# SubBus13.net
KiCad netlist of a schematic drawn in Altium Designer
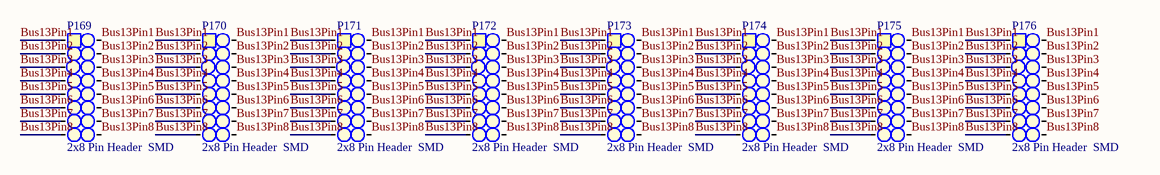
[diagram p0: SubBus13.SchDoc]

(export (version "E")
  (design (tool "Eeschema 10.0.6"))
  (components
    (comp (ref "P169")
      (value "2x8 Pin Header  SMD")
      (footprint "2X8_SMD_PH_2.54")
      (description "2.54mm, SMD")
      (libsource (lib "jclib") (part "2x8 Pin Header  SMD"))
    )
    (comp (ref "P170")
      (value "2x8 Pin Header  SMD")
      (footprint "2X8_SMD_PH_2.54")
      (description "2.54mm, SMD")
      (libsource (lib "jclib") (part "2x8 Pin Header  SMD"))
    )
    (comp (ref "P171")
      (value "2x8 Pin Header  SMD")
      (footprint "2X8_SMD_PH_2.54")
      (description "2.54mm, SMD")
      (libsource (lib "jclib") (part "2x8 Pin Header  SMD"))
    )
    (comp (ref "P172")
      (value "2x8 Pin Header  SMD")
      (footprint "2X8_SMD_PH_2.54")
      (description "2.54mm, SMD")
      (libsource (lib "jclib") (part "2x8 Pin Header  SMD"))
    )
    (comp (ref "P173")
      (value "2x8 Pin Header  SMD")
      (footprint "2X8_SMD_PH_2.54")
      (description "2.54mm, SMD")
      (libsource (lib "jclib") (part "2x8 Pin Header  SMD"))
    )
    (comp (ref "P174")
      (value "2x8 Pin Header  SMD")
      (footprint "2X8_SMD_PH_2.54")
      (description "2.54mm, SMD")
      (libsource (lib "jclib") (part "2x8 Pin Header  SMD"))
    )
    (comp (ref "P175")
      (value "2x8 Pin Header  SMD")
      (footprint "2X8_SMD_PH_2.54")
      (description "2.54mm, SMD")
      (libsource (lib "jclib") (part "2x8 Pin Header  SMD"))
    )
    (comp (ref "P176")
      (value "2x8 Pin Header  SMD")
      (footprint "2X8_SMD_PH_2.54")
      (description "2.54mm, SMD")
      (libsource (lib "jclib") (part "2x8 Pin Header  SMD"))
    )
  )
  (nets
    (net (code "1") (name "/Bus13Pin1") (class "Default")
      (node (ref "P169") (pin "1") (pinfunction "1_1") (pintype "passive"))
      (node (ref "P169") (pin "16") (pinfunction "16_16") (pintype "passive"))
      (node (ref "P170") (pin "1") (pinfunction "1_1") (pintype "passive"))
      (node (ref "P170") (pin "16") (pinfunction "16_16") (pintype "passive"))
      (node (ref "P171") (pin "1") (pinfunction "1_1") (pintype "passive"))
      (node (ref "P171") (pin "16") (pinfunction "16_16") (pintype "passive"))
      (node (ref "P172") (pin "1") (pinfunction "1_1") (pintype "passive"))
      (node (ref "P172") (pin "16") (pinfunction "16_16") (pintype "passive"))
      (node (ref "P173") (pin "1") (pinfunction "1_1") (pintype "passive"))
      (node (ref "P173") (pin "16") (pinfunction "16_16") (pintype "passive"))
      (node (ref "P174") (pin "1") (pinfunction "1_1") (pintype "passive"))
      (node (ref "P174") (pin "16") (pinfunction "16_16") (pintype "passive"))
      (node (ref "P175") (pin "1") (pinfunction "1_1") (pintype "passive"))
      (node (ref "P175") (pin "16") (pinfunction "16_16") (pintype "passive"))
      (node (ref "P176") (pin "1") (pinfunction "1_1") (pintype "passive"))
      (node (ref "P176") (pin "16") (pinfunction "16_16") (pintype "passive"))
    )
    (net (code "2") (name "/Bus13Pin2") (class "Default")
      (node (ref "P169") (pin "15") (pinfunction "15_15") (pintype "passive"))
      (node (ref "P169") (pin "2") (pinfunction "2_2") (pintype "passive"))
      (node (ref "P170") (pin "15") (pinfunction "15_15") (pintype "passive"))
      (node (ref "P170") (pin "2") (pinfunction "2_2") (pintype "passive"))
      (node (ref "P171") (pin "15") (pinfunction "15_15") (pintype "passive"))
      (node (ref "P171") (pin "2") (pinfunction "2_2") (pintype "passive"))
      (node (ref "P172") (pin "15") (pinfunction "15_15") (pintype "passive"))
      (node (ref "P172") (pin "2") (pinfunction "2_2") (pintype "passive"))
      (node (ref "P173") (pin "15") (pinfunction "15_15") (pintype "passive"))
      (node (ref "P173") (pin "2") (pinfunction "2_2") (pintype "passive"))
      (node (ref "P174") (pin "15") (pinfunction "15_15") (pintype "passive"))
      (node (ref "P174") (pin "2") (pinfunction "2_2") (pintype "passive"))
      (node (ref "P175") (pin "15") (pinfunction "15_15") (pintype "passive"))
      (node (ref "P175") (pin "2") (pinfunction "2_2") (pintype "passive"))
      (node (ref "P176") (pin "15") (pinfunction "15_15") (pintype "passive"))
      (node (ref "P176") (pin "2") (pinfunction "2_2") (pintype "passive"))
    )
    (net (code "3") (name "/Bus13Pin3") (class "Default")
      (node (ref "P169") (pin "14") (pinfunction "14_14") (pintype "passive"))
      (node (ref "P169") (pin "3") (pinfunction "3_3") (pintype "passive"))
      (node (ref "P170") (pin "14") (pinfunction "14_14") (pintype "passive"))
      (node (ref "P170") (pin "3") (pinfunction "3_3") (pintype "passive"))
      (node (ref "P171") (pin "14") (pinfunction "14_14") (pintype "passive"))
      (node (ref "P171") (pin "3") (pinfunction "3_3") (pintype "passive"))
      (node (ref "P172") (pin "14") (pinfunction "14_14") (pintype "passive"))
      (node (ref "P172") (pin "3") (pinfunction "3_3") (pintype "passive"))
      (node (ref "P173") (pin "14") (pinfunction "14_14") (pintype "passive"))
      (node (ref "P173") (pin "3") (pinfunction "3_3") (pintype "passive"))
      (node (ref "P174") (pin "14") (pinfunction "14_14") (pintype "passive"))
      (node (ref "P174") (pin "3") (pinfunction "3_3") (pintype "passive"))
      (node (ref "P175") (pin "14") (pinfunction "14_14") (pintype "passive"))
      (node (ref "P175") (pin "3") (pinfunction "3_3") (pintype "passive"))
      (node (ref "P176") (pin "14") (pinfunction "14_14") (pintype "passive"))
      (node (ref "P176") (pin "3") (pinfunction "3_3") (pintype "passive"))
    )
    (net (code "4") (name "/Bus13Pin4") (class "Default")
      (node (ref "P169") (pin "13") (pinfunction "13_13") (pintype "passive"))
      (node (ref "P169") (pin "4") (pinfunction "4_4") (pintype "passive"))
      (node (ref "P170") (pin "13") (pinfunction "13_13") (pintype "passive"))
      (node (ref "P170") (pin "4") (pinfunction "4_4") (pintype "passive"))
      (node (ref "P171") (pin "13") (pinfunction "13_13") (pintype "passive"))
      (node (ref "P171") (pin "4") (pinfunction "4_4") (pintype "passive"))
      (node (ref "P172") (pin "13") (pinfunction "13_13") (pintype "passive"))
      (node (ref "P172") (pin "4") (pinfunction "4_4") (pintype "passive"))
      (node (ref "P173") (pin "13") (pinfunction "13_13") (pintype "passive"))
      (node (ref "P173") (pin "4") (pinfunction "4_4") (pintype "passive"))
      (node (ref "P174") (pin "13") (pinfunction "13_13") (pintype "passive"))
      (node (ref "P174") (pin "4") (pinfunction "4_4") (pintype "passive"))
      (node (ref "P175") (pin "13") (pinfunction "13_13") (pintype "passive"))
      (node (ref "P175") (pin "4") (pinfunction "4_4") (pintype "passive"))
      (node (ref "P176") (pin "13") (pinfunction "13_13") (pintype "passive"))
      (node (ref "P176") (pin "4") (pinfunction "4_4") (pintype "passive"))
    )
    (net (code "5") (name "/Bus13Pin5") (class "Default")
      (node (ref "P169") (pin "12") (pinfunction "12_12") (pintype "passive"))
      (node (ref "P169") (pin "5") (pinfunction "5_5") (pintype "passive"))
      (node (ref "P170") (pin "12") (pinfunction "12_12") (pintype "passive"))
      (node (ref "P170") (pin "5") (pinfunction "5_5") (pintype "passive"))
      (node (ref "P171") (pin "12") (pinfunction "12_12") (pintype "passive"))
      (node (ref "P171") (pin "5") (pinfunction "5_5") (pintype "passive"))
      (node (ref "P172") (pin "12") (pinfunction "12_12") (pintype "passive"))
      (node (ref "P172") (pin "5") (pinfunction "5_5") (pintype "passive"))
      (node (ref "P173") (pin "12") (pinfunction "12_12") (pintype "passive"))
      (node (ref "P173") (pin "5") (pinfunction "5_5") (pintype "passive"))
      (node (ref "P174") (pin "12") (pinfunction "12_12") (pintype "passive"))
      (node (ref "P174") (pin "5") (pinfunction "5_5") (pintype "passive"))
      (node (ref "P175") (pin "12") (pinfunction "12_12") (pintype "passive"))
      (node (ref "P175") (pin "5") (pinfunction "5_5") (pintype "passive"))
      (node (ref "P176") (pin "12") (pinfunction "12_12") (pintype "passive"))
      (node (ref "P176") (pin "5") (pinfunction "5_5") (pintype "passive"))
    )
    (net (code "6") (name "/Bus13Pin6") (class "Default")
      (node (ref "P169") (pin "11") (pinfunction "11_11") (pintype "passive"))
      (node (ref "P169") (pin "6") (pinfunction "6_6") (pintype "passive"))
      (node (ref "P170") (pin "11") (pinfunction "11_11") (pintype "passive"))
      (node (ref "P170") (pin "6") (pinfunction "6_6") (pintype "passive"))
      (node (ref "P171") (pin "11") (pinfunction "11_11") (pintype "passive"))
      (node (ref "P171") (pin "6") (pinfunction "6_6") (pintype "passive"))
      (node (ref "P172") (pin "11") (pinfunction "11_11") (pintype "passive"))
      (node (ref "P172") (pin "6") (pinfunction "6_6") (pintype "passive"))
      (node (ref "P173") (pin "11") (pinfunction "11_11") (pintype "passive"))
      (node (ref "P173") (pin "6") (pinfunction "6_6") (pintype "passive"))
      (node (ref "P174") (pin "11") (pinfunction "11_11") (pintype "passive"))
      (node (ref "P174") (pin "6") (pinfunction "6_6") (pintype "passive"))
      (node (ref "P175") (pin "11") (pinfunction "11_11") (pintype "passive"))
      (node (ref "P175") (pin "6") (pinfunction "6_6") (pintype "passive"))
      (node (ref "P176") (pin "11") (pinfunction "11_11") (pintype "passive"))
      (node (ref "P176") (pin "6") (pinfunction "6_6") (pintype "passive"))
    )
    (net (code "7") (name "/Bus13Pin7") (class "Default")
      (node (ref "P169") (pin "10") (pinfunction "10_10") (pintype "passive"))
      (node (ref "P169") (pin "7") (pinfunction "7_7") (pintype "passive"))
      (node (ref "P170") (pin "10") (pinfunction "10_10") (pintype "passive"))
      (node (ref "P170") (pin "7") (pinfunction "7_7") (pintype "passive"))
      (node (ref "P171") (pin "10") (pinfunction "10_10") (pintype "passive"))
      (node (ref "P171") (pin "7") (pinfunction "7_7") (pintype "passive"))
      (node (ref "P172") (pin "10") (pinfunction "10_10") (pintype "passive"))
      (node (ref "P172") (pin "7") (pinfunction "7_7") (pintype "passive"))
      (node (ref "P173") (pin "10") (pinfunction "10_10") (pintype "passive"))
      (node (ref "P173") (pin "7") (pinfunction "7_7") (pintype "passive"))
      (node (ref "P174") (pin "10") (pinfunction "10_10") (pintype "passive"))
      (node (ref "P174") (pin "7") (pinfunction "7_7") (pintype "passive"))
      (node (ref "P175") (pin "10") (pinfunction "10_10") (pintype "passive"))
      (node (ref "P175") (pin "7") (pinfunction "7_7") (pintype "passive"))
      (node (ref "P176") (pin "10") (pinfunction "10_10") (pintype "passive"))
      (node (ref "P176") (pin "7") (pinfunction "7_7") (pintype "passive"))
    )
    (net (code "8") (name "/Bus13Pin8") (class "Default")
      (node (ref "P169") (pin "8") (pinfunction "8_8") (pintype "passive"))
      (node (ref "P169") (pin "9") (pinfunction "9_9") (pintype "passive"))
      (node (ref "P170") (pin "8") (pinfunction "8_8") (pintype "passive"))
      (node (ref "P170") (pin "9") (pinfunction "9_9") (pintype "passive"))
      (node (ref "P171") (pin "8") (pinfunction "8_8") (pintype "passive"))
      (node (ref "P171") (pin "9") (pinfunction "9_9") (pintype "passive"))
      (node (ref "P172") (pin "8") (pinfunction "8_8") (pintype "passive"))
      (node (ref "P172") (pin "9") (pinfunction "9_9") (pintype "passive"))
      (node (ref "P173") (pin "8") (pinfunction "8_8") (pintype "passive"))
      (node (ref "P173") (pin "9") (pinfunction "9_9") (pintype "passive"))
      (node (ref "P174") (pin "8") (pinfunction "8_8") (pintype "passive"))
      (node (ref "P174") (pin "9") (pinfunction "9_9") (pintype "passive"))
      (node (ref "P175") (pin "8") (pinfunction "8_8") (pintype "passive"))
      (node (ref "P175") (pin "9") (pinfunction "9_9") (pintype "passive"))
      (node (ref "P176") (pin "8") (pinfunction "8_8") (pintype "passive"))
      (node (ref "P176") (pin "9") (pinfunction "9_9") (pintype "passive"))
    )
  )
)
